# icp.net
KiCad netlist of a schematic drawn in EAGLE
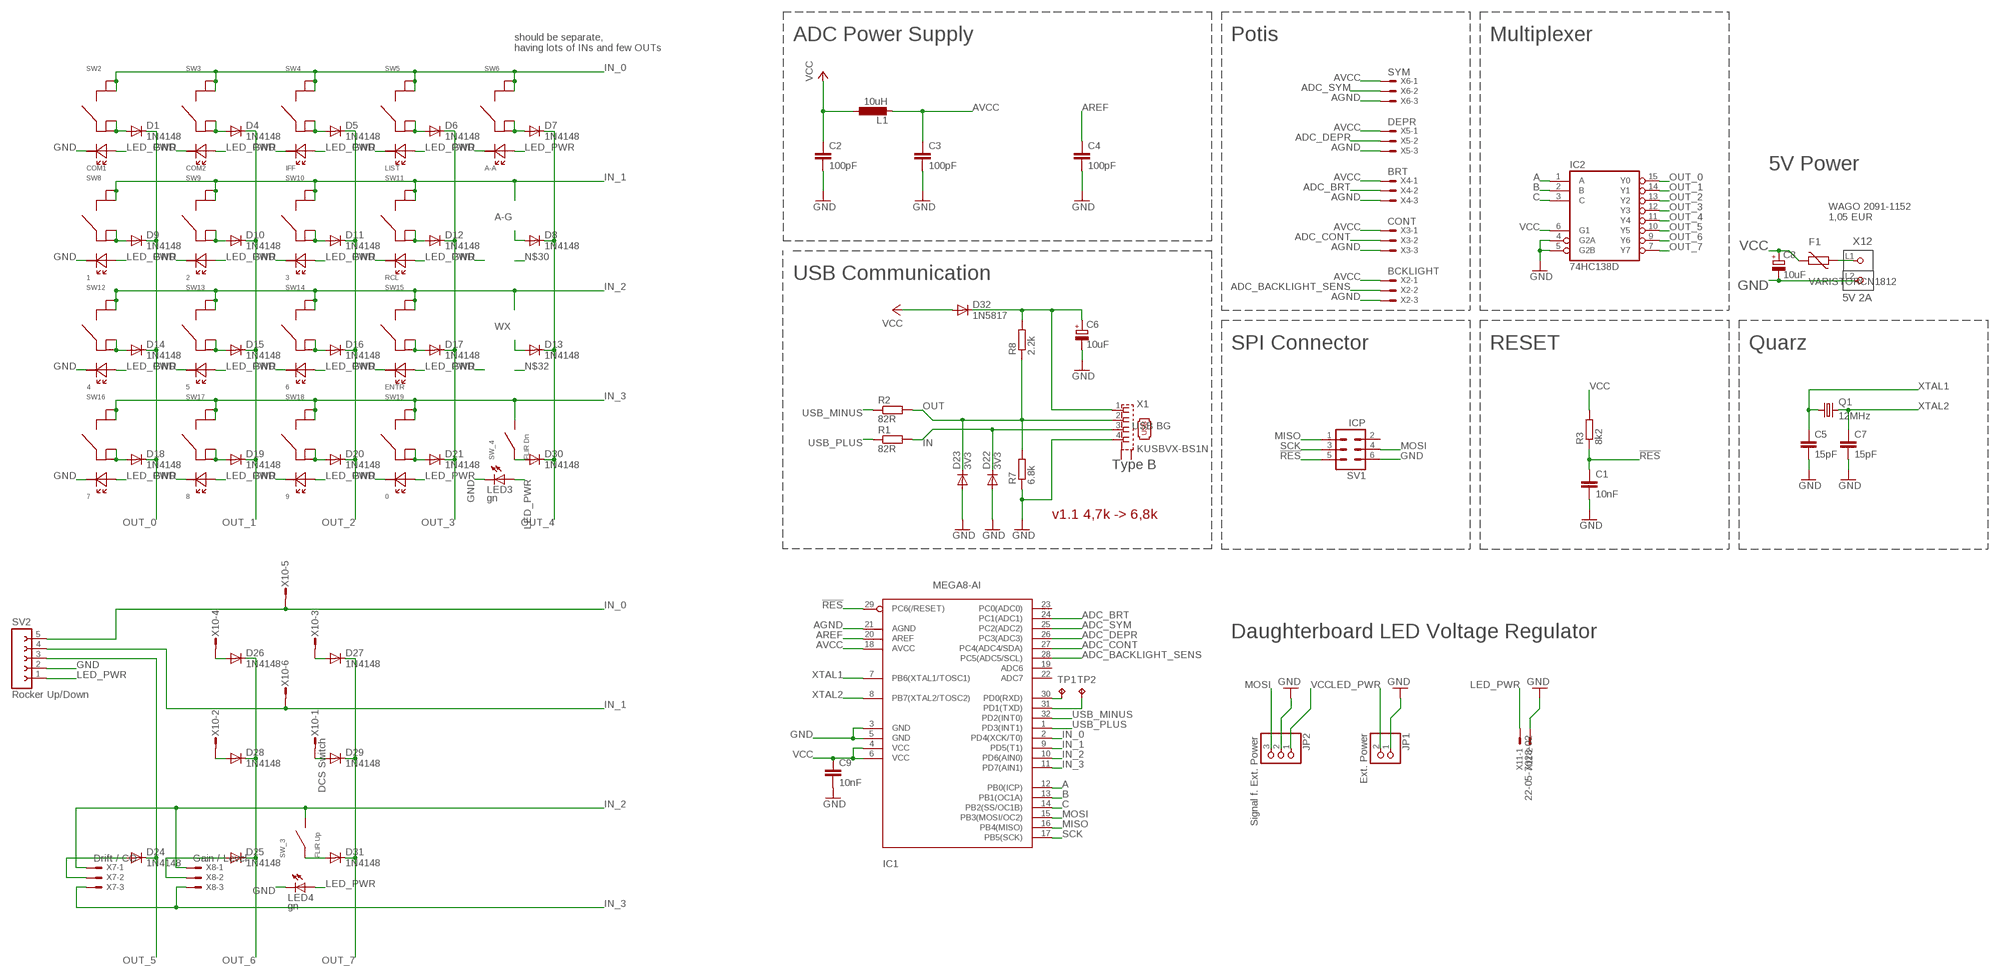
[diagram p0: schematic, sheet 1]

(export (version "E")
  (design (tool "Eeschema 10.0.6"))
  (components
    (comp (ref "C1")
      (value "10nF")
      (footprint "eagle-import:C1206")
      (libsource (lib "eagle-import") (part "C-EUC1206"))
    )
    (comp (ref "C2")
      (value "100pF")
      (footprint "eagle-import:C0805")
      (libsource (lib "eagle-import") (part "C-EUC0805"))
    )
    (comp (ref "C3")
      (value "100pF")
      (footprint "eagle-import:C0805")
      (libsource (lib "eagle-import") (part "C-EUC0805"))
    )
    (comp (ref "C4")
      (value "100pF")
      (footprint "eagle-import:C0805")
      (libsource (lib "eagle-import") (part "C-EUC0805"))
    )
    (comp (ref "C5")
      (value "15pF")
      (footprint "eagle-import:C0805")
      (libsource (lib "eagle-import") (part "C-EUC0805"))
    )
    (comp (ref "C6")
      (value "10uF")
      (footprint "eagle-import:E2-5")
      (libsource (lib "eagle-import") (part "CPOL-EUE2-5"))
    )
    (comp (ref "C7")
      (value "15pF")
      (footprint "eagle-import:C0805")
      (libsource (lib "eagle-import") (part "C-EUC0805"))
    )
    (comp (ref "C8")
      (value "10uF")
      (footprint "eagle-import:E2-5")
      (libsource (lib "eagle-import") (part "CPOL-EUE2-5"))
    )
    (comp (ref "C9")
      (value "10nF")
      (footprint "eagle-import:C1206")
      (libsource (lib "eagle-import") (part "C-EUC1206"))
    )
    (comp (ref "D1")
      (value "1N4148")
      (footprint "eagle-import:DO35-10")
      (libsource (lib "eagle-import") (part "DIODE-DO35-10"))
    )
    (comp (ref "D4")
      (value "1N4148")
      (footprint "eagle-import:DO35-10")
      (libsource (lib "eagle-import") (part "DIODE-DO35-10"))
    )
    (comp (ref "D5")
      (value "1N4148")
      (footprint "eagle-import:DO35-10")
      (libsource (lib "eagle-import") (part "DIODE-DO35-10"))
    )
    (comp (ref "D6")
      (value "1N4148")
      (footprint "eagle-import:DO35-10")
      (libsource (lib "eagle-import") (part "DIODE-DO35-10"))
    )
    (comp (ref "D7")
      (value "1N4148")
      (footprint "eagle-import:DO35-10")
      (libsource (lib "eagle-import") (part "DIODE-DO35-10"))
    )
    (comp (ref "D8")
      (value "1N4148")
      (footprint "eagle-import:DO35-10")
      (libsource (lib "eagle-import") (part "DIODE-DO35-10"))
    )
    (comp (ref "D9")
      (value "1N4148")
      (footprint "eagle-import:DO35-10")
      (libsource (lib "eagle-import") (part "DIODE-DO35-10"))
    )
    (comp (ref "D10")
      (value "1N4148")
      (footprint "eagle-import:DO35-10")
      (libsource (lib "eagle-import") (part "DIODE-DO35-10"))
    )
    (comp (ref "D11")
      (value "1N4148")
      (footprint "eagle-import:DO35-10")
      (libsource (lib "eagle-import") (part "DIODE-DO35-10"))
    )
    (comp (ref "D12")
      (value "1N4148")
      (footprint "eagle-import:DO35-10")
      (libsource (lib "eagle-import") (part "DIODE-DO35-10"))
    )
    (comp (ref "D13")
      (value "1N4148")
      (footprint "eagle-import:DO35-10")
      (libsource (lib "eagle-import") (part "DIODE-DO35-10"))
    )
    (comp (ref "D14")
      (value "1N4148")
      (footprint "eagle-import:DO35-10")
      (libsource (lib "eagle-import") (part "DIODE-DO35-10"))
    )
    (comp (ref "D15")
      (value "1N4148")
      (footprint "eagle-import:DO35-10")
      (libsource (lib "eagle-import") (part "DIODE-DO35-10"))
    )
    (comp (ref "D16")
      (value "1N4148")
      (footprint "eagle-import:DO35-10")
      (libsource (lib "eagle-import") (part "DIODE-DO35-10"))
    )
    (comp (ref "D17")
      (value "1N4148")
      (footprint "eagle-import:DO35-10")
      (libsource (lib "eagle-import") (part "DIODE-DO35-10"))
    )
    (comp (ref "D18")
      (value "1N4148")
      (footprint "eagle-import:DO35-10")
      (libsource (lib "eagle-import") (part "DIODE-DO35-10"))
    )
    (comp (ref "D19")
      (value "1N4148")
      (footprint "eagle-import:DO35-10")
      (libsource (lib "eagle-import") (part "DIODE-DO35-10"))
    )
    (comp (ref "D20")
      (value "1N4148")
      (footprint "eagle-import:DO35-10")
      (libsource (lib "eagle-import") (part "DIODE-DO35-10"))
    )
    (comp (ref "D21")
      (value "1N4148")
      (footprint "eagle-import:DO35-10")
      (libsource (lib "eagle-import") (part "DIODE-DO35-10"))
    )
    (comp (ref "D22")
      (value "3V3")
      (footprint "eagle-import:D-5")
      (libsource (lib "eagle-import") (part "DIODE-D-5"))
    )
    (comp (ref "D23")
      (value "3V3")
      (footprint "eagle-import:D-5")
      (libsource (lib "eagle-import") (part "DIODE-D-5"))
    )
    (comp (ref "D24")
      (value "1N4148")
      (footprint "eagle-import:DO35-10")
      (libsource (lib "eagle-import") (part "DIODE-DO35-10"))
    )
    (comp (ref "D25")
      (value "1N4148")
      (footprint "eagle-import:DO35-10")
      (libsource (lib "eagle-import") (part "DIODE-DO35-10"))
    )
    (comp (ref "D26")
      (value "1N4148")
      (footprint "eagle-import:DO35-10")
      (libsource (lib "eagle-import") (part "DIODE-DO35-10"))
    )
    (comp (ref "D27")
      (value "1N4148")
      (footprint "eagle-import:DO35-10")
      (libsource (lib "eagle-import") (part "DIODE-DO35-10"))
    )
    (comp (ref "D28")
      (value "1N4148")
      (footprint "eagle-import:DO35-10")
      (libsource (lib "eagle-import") (part "DIODE-DO35-10"))
    )
    (comp (ref "D29")
      (value "1N4148")
      (footprint "eagle-import:DO35-10")
      (libsource (lib "eagle-import") (part "DIODE-DO35-10"))
    )
    (comp (ref "D30")
      (value "1N4148")
      (footprint "eagle-import:DO35-10")
      (libsource (lib "eagle-import") (part "DIODE-DO35-10"))
    )
    (comp (ref "D31")
      (value "1N4148")
      (footprint "eagle-import:DO35-10")
      (libsource (lib "eagle-import") (part "DIODE-DO35-10"))
    )
    (comp (ref "D32")
      (value "1N5817")
      (footprint "eagle-import:DO35-10")
      (libsource (lib "eagle-import") (part "DIODE-DO35-10"))
    )
    (comp (ref "F1")
      (value "VARISTORCN1812")
      (footprint "eagle-import:CT_CN1812")
      (libsource (lib "eagle-import") (part "VARISTORCN1812"))
    )
    (comp (ref "IC1")
      (value "MEGA8-AI")
      (footprint "eagle-import:TQFP32-08")
      (libsource (lib "eagle-import") (part "MEGA8-AI"))
    )
    (comp (ref "IC2")
      (value "74HC138D")
      (footprint "eagle-import:SO16")
      (libsource (lib "eagle-import") (part "74138DHC"))
    )
    (comp (ref "JP1")
      (value "Ext. Power")
      (footprint "eagle-import:1X02")
      (libsource (lib "eagle-import") (part "PINHD-1X2"))
    )
    (comp (ref "JP2")
      (value "Signal f. Ext. Power")
      (footprint "eagle-import:1X03")
      (libsource (lib "eagle-import") (part "PINHD-1X3"))
    )
    (comp (ref "L1")
      (value "10uH")
      (footprint "eagle-import:0207_15")
      (libsource (lib "eagle-import") (part "L-EU0207/15"))
    )
    (comp (ref "LED3")
      (value "gn")
      (footprint "eagle-import:CHIPLED_1206")
      (libsource (lib "eagle-import") (part "LEDCHIPLED_1206"))
    )
    (comp (ref "LED4")
      (value "gn")
      (footprint "eagle-import:CHIPLED_1206")
      (libsource (lib "eagle-import") (part "LEDCHIPLED_1206"))
    )
    (comp (ref "Q1")
      (value "12MHz")
      (footprint "eagle-import:HC49U-V")
      (libsource (lib "eagle-import") (part "CRYSTALHC49U-V"))
    )
    (comp (ref "R1")
      (value "82R")
      (footprint "eagle-import:R0805W")
      (libsource (lib "eagle-import") (part "R-EU_R0805W"))
    )
    (comp (ref "R2")
      (value "82R")
      (footprint "eagle-import:R0805W")
      (libsource (lib "eagle-import") (part "R-EU_R0805W"))
    )
    (comp (ref "R3")
      (value "8k2")
      (footprint "eagle-import:R0805")
      (libsource (lib "eagle-import") (part "R-EU_R0805"))
    )
    (comp (ref "R7")
      (value "6.8k")
      (footprint "eagle-import:0207_5V")
      (libsource (lib "eagle-import") (part "R-EU_0207/5V"))
    )
    (comp (ref "R8")
      (value "2.2k")
      (footprint "eagle-import:R0805")
      (libsource (lib "eagle-import") (part "R-EU_R0805"))
    )
    (comp (ref "SV1")
      (value "ICP")
      (footprint "eagle-import:MA03-2")
      (libsource (lib "eagle-import") (part "MA03-2"))
    )
    (comp (ref "SV2")
      (value "Rocker Up/Down")
      (footprint "eagle-import:FE05-1")
      (libsource (lib "eagle-import") (part "FE05-1"))
    )
    (comp (ref "SW2")
      (value "COM1")
      (footprint "eagle-import:3FTL620")
      (libsource (lib "eagle-import") (part "3FTL620"))
    )
    (comp (ref "SW3")
      (value "COM2")
      (footprint "eagle-import:3FTL620")
      (libsource (lib "eagle-import") (part "3FTL620"))
    )
    (comp (ref "SW4")
      (value "IFF")
      (footprint "eagle-import:3FTL620")
      (libsource (lib "eagle-import") (part "3FTL620"))
    )
    (comp (ref "SW5")
      (value "LIST")
      (footprint "eagle-import:3FTL620")
      (libsource (lib "eagle-import") (part "3FTL620"))
    )
    (comp (ref "SW6")
      (value "A-A")
      (footprint "eagle-import:3FTL620")
      (libsource (lib "eagle-import") (part "3FTL620"))
    )
    (comp (ref "SW8")
      (value "1")
      (footprint "eagle-import:3FTL620")
      (libsource (lib "eagle-import") (part "3FTL620"))
    )
    (comp (ref "SW9")
      (value "2")
      (footprint "eagle-import:3FTL620")
      (libsource (lib "eagle-import") (part "3FTL620"))
    )
    (comp (ref "SW10")
      (value "3")
      (footprint "eagle-import:3FTL620")
      (libsource (lib "eagle-import") (part "3FTL620"))
    )
    (comp (ref "SW11")
      (value "RCL")
      (footprint "eagle-import:3FTL620")
      (libsource (lib "eagle-import") (part "3FTL620"))
    )
    (comp (ref "SW12")
      (value "4")
      (footprint "eagle-import:3FTL620")
      (libsource (lib "eagle-import") (part "3FTL620"))
    )
    (comp (ref "SW13")
      (value "5")
      (footprint "eagle-import:3FTL620")
      (libsource (lib "eagle-import") (part "3FTL620"))
    )
    (comp (ref "SW14")
      (value "6")
      (footprint "eagle-import:3FTL620")
      (libsource (lib "eagle-import") (part "3FTL620"))
    )
    (comp (ref "SW15")
      (value "ENTR")
      (footprint "eagle-import:3FTL620")
      (libsource (lib "eagle-import") (part "3FTL620"))
    )
    (comp (ref "SW16")
      (value "7")
      (footprint "eagle-import:3FTL620")
      (libsource (lib "eagle-import") (part "3FTL620"))
    )
    (comp (ref "SW17")
      (value "8")
      (footprint "eagle-import:3FTL620")
      (libsource (lib "eagle-import") (part "3FTL620"))
    )
    (comp (ref "SW18")
      (value "9")
      (footprint "eagle-import:3FTL620")
      (libsource (lib "eagle-import") (part "3FTL620"))
    )
    (comp (ref "SW19")
      (value "0")
      (footprint "eagle-import:3FTL620")
      (libsource (lib "eagle-import") (part "3FTL620"))
    )
    (comp (ref "SW_3")
      (value "FLIR Up")
      (footprint "eagle-import:TYPE_A")
      (libsource (lib "eagle-import") (part "APEM_SWITCH"))
    )
    (comp (ref "SW_4")
      (value "FLIR Dn")
      (footprint "eagle-import:TYPE_A")
      (libsource (lib "eagle-import") (part "APEM_SWITCH"))
    )
    (comp (ref "TP1")
      (value "TPTP06SQ")
      (footprint "eagle-import:TP06SQ")
      (libsource (lib "eagle-import") (part "TPTP06SQ"))
    )
    (comp (ref "TP2")
      (value "TPTP06SQ")
      (footprint "eagle-import:TP06SQ")
      (libsource (lib "eagle-import") (part "TPTP06SQ"))
    )
    (comp (ref "X1")
      (value "KUSBVX-BS1N")
      (footprint "eagle-import:KUSBVX-BS1N")
      (fields (field (name "REICHELT") "USB BG"))
      (libsource (lib "eagle-import") (part "KUSBVX-BS1N"))
    )
    (comp (ref "X2")
      (value "BCKLIGHT")
      (footprint "eagle-import:22-23-2031")
      (fields (field (name "MF") "MOLEX") (field (name "MPN") "22-23-2031"))
      (libsource (lib "eagle-import") (part "22-23-2031"))
    )
    (comp (ref "X3")
      (value "CONT")
      (footprint "eagle-import:22-23-2031")
      (fields (field (name "MF") "MOLEX") (field (name "MPN") "22-23-2031"))
      (libsource (lib "eagle-import") (part "22-23-2031"))
    )
    (comp (ref "X4")
      (value "BRT")
      (footprint "eagle-import:22-23-2031")
      (fields (field (name "MF") "MOLEX") (field (name "MPN") "22-23-2031"))
      (libsource (lib "eagle-import") (part "22-23-2031"))
    )
    (comp (ref "X5")
      (value "DEPR")
      (footprint "eagle-import:22-23-2031")
      (fields (field (name "MF") "MOLEX") (field (name "MPN") "22-23-2031"))
      (libsource (lib "eagle-import") (part "22-23-2031"))
    )
    (comp (ref "X6")
      (value "SYM")
      (footprint "eagle-import:22-23-2031")
      (fields (field (name "MF") "MOLEX") (field (name "MPN") "22-23-2031"))
      (libsource (lib "eagle-import") (part "22-23-2031"))
    )
    (comp (ref "X7")
      (value "Drift / CO")
      (footprint "eagle-import:22-23-2031")
      (fields
        (field (name "MF") "MOLEX")
        (field (name "MPN") "22-23-2031")
        (field (name "MF_1") "MOLEX")
        (field (name "MPN_1") "22-23-2031")
        (field (name "OC_FARNELL") "1462950")
        (field (name "OC_NEWARK") "30C0862")
      )
      (libsource (lib "eagle-import") (part "22-23-2031"))
    )
    (comp (ref "X8")
      (value "Gain / Level")
      (footprint "eagle-import:22-23-2031")
      (fields
        (field (name "MF") "MOLEX")
        (field (name "MPN") "22-23-2031")
        (field (name "MF_1") "MOLEX")
        (field (name "MPN_1") "22-23-2031")
        (field (name "OC_FARNELL") "1462950")
        (field (name "OC_NEWARK") "30C0862")
      )
      (libsource (lib "eagle-import") (part "22-23-2031"))
    )
    (comp (ref "X10")
      (value "DCS Switch")
      (footprint "eagle-import:MICROMATCH-6")
      (fields (field (name "MPN") "7-215464-6"))
      (libsource (lib "eagle-import") (part "MICROMATCH-6"))
    )
    (comp (ref "X11")
      (value "22-05-7028-02")
      (footprint "eagle-import:7395-02")
      (fields (field (name "OC_FARNELL") "9731601") (field (name "OC_NEWARK") "unknown"))
      (libsource (lib "eagle-import") (part "22-?-0205-7028"))
    )
    (comp (ref "X12")
      (value "5V 2A")
      (footprint "eagle-import:P-2091-1152")
      (libsource (lib "eagle-import") (part "2091-1152"))
    )
  )
  (nets
    (net (code "1") (name "/A") (class "Default")
      (node (ref "IC1") (pin "12") (pinfunction "PB0(ICP)_12") (pintype "bidirectional"))
      (node (ref "IC2") (pin "1") (pinfunction "A_1") (pintype "input"))
    )
    (net (code "2") (name "/ADC_BACKLIGHT_SENS") (class "Default")
      (node (ref "IC1") (pin "28") (pinfunction "PC5(ADC5/SCL)_28") (pintype "bidirectional"))
      (node (ref "X2") (pin "2") (pinfunction "S_2") (pintype "passive"))
    )
    (net (code "3") (name "/ADC_BRT") (class "Default")
      (node (ref "IC1") (pin "24") (pinfunction "PC1(ADC1)_24") (pintype "bidirectional"))
      (node (ref "X4") (pin "2") (pinfunction "S_2") (pintype "passive"))
    )
    (net (code "4") (name "/ADC_CONT") (class "Default")
      (node (ref "IC1") (pin "27") (pinfunction "PC4(ADC4/SDA)_27") (pintype "bidirectional"))
      (node (ref "X3") (pin "2") (pinfunction "S_2") (pintype "passive"))
    )
    (net (code "5") (name "/ADC_DEPR") (class "Default")
      (node (ref "IC1") (pin "26") (pinfunction "PC3(ADC3)_26") (pintype "bidirectional"))
      (node (ref "X5") (pin "2") (pinfunction "S_2") (pintype "passive"))
    )
    (net (code "6") (name "/ADC_SYM") (class "Default")
      (node (ref "IC1") (pin "25") (pinfunction "PC2(ADC2)_25") (pintype "bidirectional"))
      (node (ref "X6") (pin "2") (pinfunction "S_2") (pintype "passive"))
    )
    (net (code "7") (name "/AGND") (class "Default")
      (node (ref "IC1") (pin "21") (pinfunction "AGND_21") (pintype "bidirectional"))
      (node (ref "X2") (pin "3") (pinfunction "S_3") (pintype "passive"))
      (node (ref "X3") (pin "3") (pinfunction "S_3") (pintype "passive"))
      (node (ref "X4") (pin "3") (pinfunction "S_3") (pintype "passive"))
      (node (ref "X5") (pin "3") (pinfunction "S_3") (pintype "passive"))
      (node (ref "X6") (pin "3") (pinfunction "S_3") (pintype "passive"))
    )
    (net (code "8") (name "/AREF") (class "Default")
      (node (ref "C4") (pin "1") (pinfunction "1_1") (pintype "passive"))
      (node (ref "IC1") (pin "20") (pinfunction "AREF_20") (pintype "bidirectional"))
    )
    (net (code "9") (name "/AVCC") (class "Default")
      (node (ref "C3") (pin "1") (pinfunction "1_1") (pintype "passive"))
      (node (ref "IC1") (pin "18") (pinfunction "AVCC_18") (pintype "bidirectional"))
      (node (ref "L1") (pin "2") (pinfunction "2_2") (pintype "passive"))
      (node (ref "X2") (pin "1") (pinfunction "S_1") (pintype "passive"))
      (node (ref "X3") (pin "1") (pinfunction "S_1") (pintype "passive"))
      (node (ref "X4") (pin "1") (pinfunction "S_1") (pintype "passive"))
      (node (ref "X5") (pin "1") (pinfunction "S_1") (pintype "passive"))
      (node (ref "X6") (pin "1") (pinfunction "S_1") (pintype "passive"))
    )
    (net (code "10") (name "/B") (class "Default")
      (node (ref "IC1") (pin "13") (pinfunction "PB1(OC1A)_13") (pintype "bidirectional"))
      (node (ref "IC2") (pin "2") (pinfunction "B_2") (pintype "input"))
    )
    (net (code "11") (name "/C") (class "Default")
      (node (ref "IC1") (pin "14") (pinfunction "PB2(SS/OC1B)_14") (pintype "bidirectional"))
      (node (ref "IC2") (pin "3") (pinfunction "C_3") (pintype "input"))
    )
    (net (code "12") (name "/IN") (class "Default")
      (node (ref "D22") (pin "C") (pinfunction "C_C") (pintype "passive"))
      (node (ref "R1") (pin "2") (pinfunction "2_2") (pintype "passive"))
      (node (ref "X1") (pin "3") (pinfunction "3_3") (pintype "passive"))
    )
    (net (code "13") (name "/IN_0") (class "Default")
      (node (ref "IC1") (pin "2") (pinfunction "PD4(XCK/T0)_2") (pintype "bidirectional"))
      (node (ref "SV2") (pin "5") (pinfunction "5_5") (pintype "passive"))
      (node (ref "SW2") (pin "P$1") (pinfunction "P$1_P$1") (pintype "passive"))
      (node (ref "SW2") (pin "P$3") (pinfunction "P$3_P$3") (pintype "passive"))
      (node (ref "SW3") (pin "P$1") (pinfunction "P$1_P$1") (pintype "passive"))
      (node (ref "SW3") (pin "P$3") (pinfunction "P$3_P$3") (pintype "passive"))
      (node (ref "SW4") (pin "P$1") (pinfunction "P$1_P$1") (pintype "passive"))
      (node (ref "SW4") (pin "P$3") (pinfunction "P$3_P$3") (pintype "passive"))
      (node (ref "SW5") (pin "P$1") (pinfunction "P$1_P$1") (pintype "passive"))
      (node (ref "SW5") (pin "P$3") (pinfunction "P$3_P$3") (pintype "passive"))
      (node (ref "SW6") (pin "P$1") (pinfunction "P$1_P$1") (pintype "passive"))
      (node (ref "SW6") (pin "P$3") (pinfunction "P$3_P$3") (pintype "passive"))
      (node (ref "X10") (pin "5") (pinfunction "S_5") (pintype "passive"))
    )
    (net (code "14") (name "/IN_1") (class "Default")
      (node (ref "IC1") (pin "9") (pinfunction "PD5(T1)_9") (pintype "bidirectional"))
      (node (ref "SV2") (pin "4") (pinfunction "4_4") (pintype "passive"))
      (node (ref "SW10") (pin "P$1") (pinfunction "P$1_P$1") (pintype "passive"))
      (node (ref "SW10") (pin "P$3") (pinfunction "P$3_P$3") (pintype "passive"))
      (node (ref "SW11") (pin "P$1") (pinfunction "P$1_P$1") (pintype "passive"))
      (node (ref "SW11") (pin "P$3") (pinfunction "P$3_P$3") (pintype "passive"))
      (node (ref "SW8") (pin "P$1") (pinfunction "P$1_P$1") (pintype "passive"))
      (node (ref "SW8") (pin "P$3") (pinfunction "P$3_P$3") (pintype "passive"))
      (node (ref "SW9") (pin "P$1") (pinfunction "P$1_P$1") (pintype "passive"))
      (node (ref "SW9") (pin "P$3") (pinfunction "P$3_P$3") (pintype "passive"))
      (node (ref "X10") (pin "6") (pinfunction "S_6") (pintype "passive"))
    )
    (net (code "15") (name "/IN_2") (class "Default")
      (node (ref "IC1") (pin "10") (pinfunction "PD6(AIN0)_10") (pintype "bidirectional"))
      (node (ref "SW12") (pin "P$1") (pinfunction "P$1_P$1") (pintype "passive"))
      (node (ref "SW12") (pin "P$3") (pinfunction "P$3_P$3") (pintype "passive"))
      (node (ref "SW13") (pin "P$1") (pinfunction "P$1_P$1") (pintype "passive"))
      (node (ref "SW13") (pin "P$3") (pinfunction "P$3_P$3") (pintype "passive"))
      (node (ref "SW14") (pin "P$1") (pinfunction "P$1_P$1") (pintype "passive"))
      (node (ref "SW14") (pin "P$3") (pinfunction "P$3_P$3") (pintype "passive"))
      (node (ref "SW15") (pin "P$1") (pinfunction "P$1_P$1") (pintype "passive"))
      (node (ref "SW15") (pin "P$3") (pinfunction "P$3_P$3") (pintype "passive"))
      (node (ref "SW_3") (pin "P$1") (pinfunction "P$1_P$1") (pintype "passive"))
      (node (ref "X7") (pin "1") (pinfunction "S_1") (pintype "passive"))
      (node (ref "X8") (pin "1") (pinfunction "S_1") (pintype "passive"))
    )
    (net (code "16") (name "/IN_3") (class "Default")
      (node (ref "IC1") (pin "11") (pinfunction "PD7(AIN1)_11") (pintype "bidirectional"))
      (node (ref "SW16") (pin "P$1") (pinfunction "P$1_P$1") (pintype "passive"))
      (node (ref "SW16") (pin "P$3") (pinfunction "P$3_P$3") (pintype "passive"))
      (node (ref "SW17") (pin "P$1") (pinfunction "P$1_P$1") (pintype "passive"))
      (node (ref "SW17") (pin "P$3") (pinfunction "P$3_P$3") (pintype "passive"))
      (node (ref "SW18") (pin "P$1") (pinfunction "P$1_P$1") (pintype "passive"))
      (node (ref "SW18") (pin "P$3") (pinfunction "P$3_P$3") (pintype "passive"))
      (node (ref "SW19") (pin "P$1") (pinfunction "P$1_P$1") (pintype "passive"))
      (node (ref "SW19") (pin "P$3") (pinfunction "P$3_P$3") (pintype "passive"))
      (node (ref "SW_4") (pin "P$1") (pinfunction "P$1_P$1") (pintype "passive"))
      (node (ref "X7") (pin "3") (pinfunction "S_3") (pintype "passive"))
      (node (ref "X8") (pin "3") (pinfunction "S_3") (pintype "passive"))
    )
    (net (code "17") (name "/LED_PWR") (class "Default")
      (node (ref "JP1") (pin "2") (pinfunction "2_2") (pintype "passive"))
      (node (ref "LED3") (pin "A") (pinfunction "A_A") (pintype "passive"))
      (node (ref "LED4") (pin "A") (pinfunction "A_A") (pintype "passive"))
      (node (ref "SV2") (pin "1") (pinfunction "1_1") (pintype "passive"))
      (node (ref "SW10") (pin "P$5") (pinfunction "LED$3_P$5") (pintype "passive"))
      (node (ref "SW11") (pin "P$5") (pinfunction "LED$3_P$5") (pintype "passive"))
      (node (ref "SW12") (pin "P$5") (pinfunction "LED$3_P$5") (pintype "passive"))
      (node (ref "SW13") (pin "P$5") (pinfunction "LED$3_P$5") (pintype "passive"))
      (node (ref "SW14") (pin "P$5") (pinfunction "LED$3_P$5") (pintype "passive"))
      (node (ref "SW15") (pin "P$5") (pinfunction "LED$3_P$5") (pintype "passive"))
      (node (ref "SW16") (pin "P$5") (pinfunction "LED$3_P$5") (pintype "passive"))
      (node (ref "SW17") (pin "P$5") (pinfunction "LED$3_P$5") (pintype "passive"))
      (node (ref "SW18") (pin "P$5") (pinfunction "LED$3_P$5") (pintype "passive"))
      (node (ref "SW19") (pin "P$5") (pinfunction "LED$3_P$5") (pintype "passive"))
      (node (ref "SW2") (pin "P$5") (pinfunction "LED$3_P$5") (pintype "passive"))
      (node (ref "SW3") (pin "P$5") (pinfunction "LED$3_P$5") (pintype "passive"))
      (node (ref "SW4") (pin "P$5") (pinfunction "LED$3_P$5") (pintype "passive"))
      (node (ref "SW5") (pin "P$5") (pinfunction "LED$3_P$5") (pintype "passive"))
      (node (ref "SW6") (pin "P$5") (pinfunction "LED$3_P$5") (pintype "passive"))
      (node (ref "SW8") (pin "P$5") (pinfunction "LED$3_P$5") (pintype "passive"))
      (node (ref "SW9") (pin "P$5") (pinfunction "LED$3_P$5") (pintype "passive"))
      (node (ref "X11") (pin "1") (pinfunction "S_1") (pintype "passive"))
    )
    (net (code "18") (name "/MISO") (class "Default")
      (node (ref "IC1") (pin "16") (pinfunction "PB4(MISO)_16") (pintype "bidirectional"))
      (node (ref "SV1") (pin "1") (pinfunction "1_1") (pintype "passive"))
    )
    (net (code "19") (name "/MOSI") (class "Default")
      (node (ref "IC1") (pin "15") (pinfunction "PB3(MOSI/OC2)_15") (pintype "bidirectional"))
      (node (ref "JP2") (pin "3") (pinfunction "3_3") (pintype "passive"))
      (node (ref "SV1") (pin "4") (pinfunction "4_4") (pintype "passive"))
    )
    (net (code "22") (name "/OUT") (class "Default")
      (node (ref "D23") (pin "C") (pinfunction "C_C") (pintype "passive"))
      (node (ref "R2") (pin "2") (pinfunction "2_2") (pintype "passive"))
      (node (ref "R7") (pin "2") (pinfunction "2_2") (pintype "passive"))
      (node (ref "R8") (pin "1") (pinfunction "1_1") (pintype "passive"))
      (node (ref "X1") (pin "2") (pinfunction "2_2") (pintype "passive"))
    )
    (net (code "23") (name "/OUT_0") (class "Default")
      (node (ref "D1") (pin "C") (pinfunction "C_C") (pintype "passive"))
      (node (ref "D14") (pin "C") (pinfunction "C_C") (pintype "passive"))
      (node (ref "D18") (pin "C") (pinfunction "C_C") (pintype "passive"))
      (node (ref "D9") (pin "C") (pinfunction "C_C") (pintype "passive"))
      (node (ref "IC2") (pin "15") (pinfunction "Y0_15") (pintype "output"))
    )
    (net (code "24") (name "/OUT_1") (class "Default")
      (node (ref "D10") (pin "C") (pinfunction "C_C") (pintype "passive"))
      (node (ref "D15") (pin "C") (pinfunction "C_C") (pintype "passive"))
      (node (ref "D19") (pin "C") (pinfunction "C_C") (pintype "passive"))
      (node (ref "D4") (pin "C") (pinfunction "C_C") (pintype "passive"))
      (node (ref "IC2") (pin "14") (pinfunction "Y1_14") (pintype "output"))
    )
    (net (code "25") (name "/OUT_2") (class "Default")
      (node (ref "D11") (pin "C") (pinfunction "C_C") (pintype "passive"))
      (node (ref "D16") (pin "C") (pinfunction "C_C") (pintype "passive"))
      (node (ref "D20") (pin "C") (pinfunction "C_C") (pintype "passive"))
      (node (ref "D5") (pin "C") (pinfunction "C_C") (pintype "passive"))
      (node (ref "IC2") (pin "13") (pinfunction "Y2_13") (pintype "output"))
    )
    (net (code "26") (name "/OUT_3") (class "Default")
      (node (ref "D12") (pin "C") (pinfunction "C_C") (pintype "passive"))
      (node (ref "D17") (pin "C") (pinfunction "C_C") (pintype "passive"))
      (node (ref "D21") (pin "C") (pinfunction "C_C") (pintype "passive"))
      (node (ref "D6") (pin "C") (pinfunction "C_C") (pintype "passive"))
      (node (ref "IC2") (pin "12") (pinfunction "Y3_12") (pintype "output"))
    )
    (net (code "27") (name "/OUT_4") (class "Default")
      (node (ref "D13") (pin "C") (pinfunction "C_C") (pintype "passive"))
      (node (ref "D30") (pin "C") (pinfunction "C_C") (pintype "passive"))
      (node (ref "D7") (pin "C") (pinfunction "C_C") (pintype "passive"))
      (node (ref "D8") (pin "C") (pinfunction "C_C") (pintype "passive"))
      (node (ref "IC2") (pin "11") (pinfunction "Y4_11") (pintype "output"))
    )
    (net (code "28") (name "/OUT_5") (class "Default")
      (node (ref "D24") (pin "C") (pinfunction "C_C") (pintype "passive"))
      (node (ref "IC2") (pin "10") (pinfunction "Y5_10") (pintype "output"))
      (node (ref "SV2") (pin "3") (pinfunction "3_3") (pintype "passive"))
    )
    (net (code "29") (name "/OUT_6") (class "Default")
      (node (ref "D25") (pin "C") (pinfunction "C_C") (pintype "passive"))
      (node (ref "D26") (pin "C") (pinfunction "C_C") (pintype "passive"))
      (node (ref "D28") (pin "C") (pinfunction "C_C") (pintype "passive"))
      (node (ref "IC2") (pin "9") (pinfunction "Y6_9") (pintype "output"))
    )
    (net (code "30") (name "/OUT_7") (class "Default")
      (node (ref "D27") (pin "C") (pinfunction "C_C") (pintype "passive"))
      (node (ref "D29") (pin "C") (pinfunction "C_C") (pintype "passive"))
      (node (ref "D31") (pin "C") (pinfunction "C_C") (pintype "passive"))
      (node (ref "IC2") (pin "7") (pinfunction "Y7_7") (pintype "output"))
    )
    (net (code "31") (name "/SCK") (class "Default")
      (node (ref "IC1") (pin "17") (pinfunction "PB5(SCK)_17") (pintype "bidirectional"))
      (node (ref "SV1") (pin "3") (pinfunction "3_3") (pintype "passive"))
    )
    (net (code "32") (name "/USB_MINUS") (class "Default")
      (node (ref "IC1") (pin "32") (pinfunction "PD2(INT0)_32") (pintype "bidirectional"))
      (node (ref "R2") (pin "1") (pinfunction "1_1") (pintype "passive"))
    )
    (net (code "33") (name "/USB_PLUS") (class "Default")
      (node (ref "IC1") (pin "1") (pinfunction "PD3(INT1)_1") (pintype "bidirectional"))
      (node (ref "R1") (pin "1") (pinfunction "1_1") (pintype "passive"))
    )
    (net (code "34") (name "/XTAL1") (class "Default")
      (node (ref "C5") (pin "1") (pinfunction "1_1") (pintype "passive"))
      (node (ref "IC1") (pin "7") (pinfunction "PB6(XTAL1/TOSC1)_7") (pintype "bidirectional"))
      (node (ref "Q1") (pin "1") (pinfunction "1_1") (pintype "passive"))
    )
    (net (code "35") (name "/XTAL2") (class "Default")
      (node (ref "C7") (pin "1") (pinfunction "1_1") (pintype "passive"))
      (node (ref "IC1") (pin "8") (pinfunction "PB7(XTAL2/TOSC2)_8") (pintype "bidirectional"))
      (node (ref "Q1") (pin "2") (pinfunction "2_2") (pintype "passive"))
    )
    (net (code "36") (name "/~{RES}") (class "Default")
      (node (ref "C1") (pin "1") (pinfunction "1_1") (pintype "passive"))
      (node (ref "IC1") (pin "29") (pinfunction "PC6(/RESET)_29") (pintype "bidirectional"))
      (node (ref "R3") (pin "1") (pinfunction "1_1") (pintype "passive"))
      (node (ref "SV1") (pin "5") (pinfunction "5_5") (pintype "passive"))
    )
    (net (code "37") (name "GND") (class "Default")
      (node (ref "C1") (pin "2") (pinfunction "2_2") (pintype "passive"))
      (node (ref "C2") (pin "2") (pinfunction "2_2") (pintype "passive"))
      (node (ref "C3") (pin "2") (pinfunction "2_2") (pintype "passive"))
      (node (ref "C4") (pin "2") (pinfunction "2_2") (pintype "passive"))
      (node (ref "C5") (pin "2") (pinfunction "2_2") (pintype "passive"))
      (node (ref "C6") (pin "-") (pinfunction "-_-") (pintype "passive"))
      (node (ref "C7") (pin "2") (pinfunction "2_2") (pintype "passive"))
      (node (ref "C8") (pin "-") (pinfunction "-_-") (pintype "passive"))
      (node (ref "C9") (pin "2") (pinfunction "2_2") (pintype "passive"))
      (node (ref "D22") (pin "A") (pinfunction "A_A") (pintype "passive"))
      (node (ref "D23") (pin "A") (pinfunction "A_A") (pintype "passive"))
      (node (ref "IC1") (pin "3") (pinfunction "GND_3") (pintype "bidirectional"))
      (node (ref "IC1") (pin "5") (pinfunction "GND_5") (pintype "bidirectional"))
      (node (ref "IC2") (pin "4") (pinfunction "G2A_4") (pintype "input"))
      (node (ref "IC2") (pin "5") (pinfunction "G2B_5") (pintype "input"))
      (node (ref "JP1") (pin "1") (pinfunction "1_1") (pintype "passive"))
      (node (ref "JP2") (pin "2") (pinfunction "2_2") (pintype "passive"))
      (node (ref "LED3") (pin "C") (pinfunction "C_C") (pintype "passive"))
      (node (ref "LED4") (pin "C") (pinfunction "C_C") (pintype "passive"))
      (node (ref "R7") (pin "1") (pinfunction "1_1") (pintype "passive"))
      (node (ref "SV1") (pin "6") (pinfunction "6_6") (pintype "passive"))
      (node (ref "SV2") (pin "2") (pinfunction "2_2") (pintype "passive"))
      (node (ref "SW10") (pin "P$6") (pinfunction "LED$4_P$6") (pintype "passive"))
      (node (ref "SW11") (pin "P$6") (pinfunction "LED$4_P$6") (pintype "passive"))
      (node (ref "SW12") (pin "P$6") (pinfunction "LED$4_P$6") (pintype "passive"))
      (node (ref "SW13") (pin "P$6") (pinfunction "LED$4_P$6") (pintype "passive"))
      (node (ref "SW14") (pin "P$6") (pinfunction "LED$4_P$6") (pintype "passive"))
      (node (ref "SW15") (pin "P$6") (pinfunction "LED$4_P$6") (pintype "passive"))
      (node (ref "SW16") (pin "P$6") (pinfunction "LED$4_P$6") (pintype "passive"))
      (node (ref "SW17") (pin "P$6") (pinfunction "LED$4_P$6") (pintype "passive"))
      (node (ref "SW18") (pin "P$6") (pinfunction "LED$4_P$6") (pintype "passive"))
      (node (ref "SW19") (pin "P$6") (pinfunction "LED$4_P$6") (pintype "passive"))
      (node (ref "SW2") (pin "P$6") (pinfunction "LED$4_P$6") (pintype "passive"))
      (node (ref "SW3") (pin "P$6") (pinfunction "LED$4_P$6") (pintype "passive"))
      (node (ref "SW4") (pin "P$6") (pinfunction "LED$4_P$6") (pintype "passive"))
      (node (ref "SW5") (pin "P$6") (pinfunction "LED$4_P$6") (pintype "passive"))
      (node (ref "SW6") (pin "P$6") (pinfunction "LED$4_P$6") (pintype "passive"))
      (node (ref "SW8") (pin "P$6") (pinfunction "LED$4_P$6") (pintype "passive"))
      (node (ref "SW9") (pin "P$6") (pinfunction "LED$4_P$6") (pintype "passive"))
      (node (ref "X1") (pin "4") (pinfunction "4_4") (pintype "passive"))
      (node (ref "X11") (pin "2") (pinfunction "S_2") (pintype "passive"))
      (node (ref "X12") (pin "L2") (pinfunction "P2_L2") (pintype "bidirectional"))
    )
    (net (code "38") (name "Net-(C6-Pad+)") (class "Default")
      (node (ref "C6") (pin "+") (pinfunction "+_+") (pintype "passive"))
      (node (ref "D32") (pin "C") (pinfunction "C_C") (pintype "passive"))
      (node (ref "R8") (pin "2") (pinfunction "2_2") (pintype "passive"))
      (node (ref "X1") (pin "1") (pinfunction "1_1") (pintype "passive"))
    )
    (net (code "39") (name "Net-(D1-PadA)") (class "Default")
      (node (ref "D1") (pin "A") (pinfunction "A_A") (pintype "passive"))
      (node (ref "SW2") (pin "P$2") (pinfunction "P$2_P$2") (pintype "passive"))
      (node (ref "SW2") (pin "P$4") (pinfunction "P$4_P$4") (pintype "passive"))
    )
    (net (code "40") (name "Net-(D4-PadA)") (class "Default")
      (node (ref "D4") (pin "A") (pinfunction "A_A") (pintype "passive"))
      (node (ref "SW3") (pin "P$2") (pinfunction "P$2_P$2") (pintype "passive"))
      (node (ref "SW3") (pin "P$4") (pinfunction "P$4_P$4") (pintype "passive"))
    )
    (net (code "41") (name "Net-(D5-PadA)") (class "Default")
      (node (ref "D5") (pin "A") (pinfunction "A_A") (pintype "passive"))
      (node (ref "SW4") (pin "P$2") (pinfunction "P$2_P$2") (pintype "passive"))
      (node (ref "SW4") (pin "P$4") (pinfunction "P$4_P$4") (pintype "passive"))
    )
    (net (code "42") (name "Net-(D6-PadA)") (class "Default")
      (node (ref "D6") (pin "A") (pinfunction "A_A") (pintype "passive"))
      (node (ref "SW5") (pin "P$2") (pinfunction "P$2_P$2") (pintype "passive"))
      (node (ref "SW5") (pin "P$4") (pinfunction "P$4_P$4") (pintype "passive"))
    )
    (net (code "43") (name "Net-(D7-PadA)") (class "Default")
      (node (ref "D7") (pin "A") (pinfunction "A_A") (pintype "passive"))
      (node (ref "SW6") (pin "P$2") (pinfunction "P$2_P$2") (pintype "passive"))
      (node (ref "SW6") (pin "P$4") (pinfunction "P$4_P$4") (pintype "passive"))
    )
    (net (code "44") (name "Net-(D9-PadA)") (class "Default")
      (node (ref "D9") (pin "A") (pinfunction "A_A") (pintype "passive"))
      (node (ref "SW8") (pin "P$2") (pinfunction "P$2_P$2") (pintype "passive"))
      (node (ref "SW8") (pin "P$4") (pinfunction "P$4_P$4") (pintype "passive"))
    )
    (net (code "45") (name "Net-(D10-PadA)") (class "Default")
      (node (ref "D10") (pin "A") (pinfunction "A_A") (pintype "passive"))
      (node (ref "SW9") (pin "P$2") (pinfunction "P$2_P$2") (pintype "passive"))
      (node (ref "SW9") (pin "P$4") (pinfunction "P$4_P$4") (pintype "passive"))
    )
    (net (code "46") (name "Net-(D11-PadA)") (class "Default")
      (node (ref "D11") (pin "A") (pinfunction "A_A") (pintype "passive"))
      (node (ref "SW10") (pin "P$2") (pinfunction "P$2_P$2") (pintype "passive"))
      (node (ref "SW10") (pin "P$4") (pinfunction "P$4_P$4") (pintype "passive"))
    )
    (net (code "47") (name "Net-(D12-PadA)") (class "Default")
      (node (ref "D12") (pin "A") (pinfunction "A_A") (pintype "passive"))
      (node (ref "SW11") (pin "P$2") (pinfunction "P$2_P$2") (pintype "passive"))
      (node (ref "SW11") (pin "P$4") (pinfunction "P$4_P$4") (pintype "passive"))
    )
    (net (code "48") (name "Net-(D14-PadA)") (class "Default")
      (node (ref "D14") (pin "A") (pinfunction "A_A") (pintype "passive"))
      (node (ref "SW12") (pin "P$2") (pinfunction "P$2_P$2") (pintype "passive"))
      (node (ref "SW12") (pin "P$4") (pinfunction "P$4_P$4") (pintype "passive"))
    )
    (net (code "49") (name "Net-(D15-PadA)") (class "Default")
      (node (ref "D15") (pin "A") (pinfunction "A_A") (pintype "passive"))
      (node (ref "SW13") (pin "P$2") (pinfunction "P$2_P$2") (pintype "passive"))
      (node (ref "SW13") (pin "P$4") (pinfunction "P$4_P$4") (pintype "passive"))
    )
    (net (code "50") (name "Net-(D16-PadA)") (class "Default")
      (node (ref "D16") (pin "A") (pinfunction "A_A") (pintype "passive"))
      (node (ref "SW14") (pin "P$2") (pinfunction "P$2_P$2") (pintype "passive"))
      (node (ref "SW14") (pin "P$4") (pinfunction "P$4_P$4") (pintype "passive"))
    )
    (net (code "51") (name "Net-(D17-PadA)") (class "Default")
      (node (ref "D17") (pin "A") (pinfunction "A_A") (pintype "passive"))
      (node (ref "SW15") (pin "P$2") (pinfunction "P$2_P$2") (pintype "passive"))
      (node (ref "SW15") (pin "P$4") (pinfunction "P$4_P$4") (pintype "passive"))
    )
    (net (code "52") (name "Net-(D18-PadA)") (class "Default")
      (node (ref "D18") (pin "A") (pinfunction "A_A") (pintype "passive"))
      (node (ref "SW16") (pin "P$2") (pinfunction "P$2_P$2") (pintype "passive"))
      (node (ref "SW16") (pin "P$4") (pinfunction "P$4_P$4") (pintype "passive"))
    )
    (net (code "53") (name "Net-(D19-PadA)") (class "Default")
      (node (ref "D19") (pin "A") (pinfunction "A_A") (pintype "passive"))
      (node (ref "SW17") (pin "P$2") (pinfunction "P$2_P$2") (pintype "passive"))
      (node (ref "SW17") (pin "P$4") (pinfunction "P$4_P$4") (pintype "passive"))
    )
    (net (code "54") (name "Net-(D20-PadA)") (class "Default")
      (node (ref "D20") (pin "A") (pinfunction "A_A") (pintype "passive"))
      (node (ref "SW18") (pin "P$2") (pinfunction "P$2_P$2") (pintype "passive"))
      (node (ref "SW18") (pin "P$4") (pinfunction "P$4_P$4") (pintype "passive"))
    )
    (net (code "55") (name "Net-(D21-PadA)") (class "Default")
      (node (ref "D21") (pin "A") (pinfunction "A_A") (pintype "passive"))
      (node (ref "SW19") (pin "P$2") (pinfunction "P$2_P$2") (pintype "passive"))
      (node (ref "SW19") (pin "P$4") (pinfunction "P$4_P$4") (pintype "passive"))
    )
    (net (code "56") (name "Net-(D30-PadA)") (class "Default")
      (node (ref "D30") (pin "A") (pinfunction "A_A") (pintype "passive"))
      (node (ref "SW_4") (pin "P$2") (pinfunction "P$2_P$2") (pintype "passive"))
    )
    (net (code "57") (name "Net-(D31-PadA)") (class "Default")
      (node (ref "D31") (pin "A") (pinfunction "A_A") (pintype "passive"))
      (node (ref "SW_3") (pin "P$2") (pinfunction "P$2_P$2") (pintype "passive"))
    )
    (net (code "58") (name "Net-(IC1-PD0(RXD))") (class "Default")
      (node (ref "IC1") (pin "30") (pinfunction "PD0(RXD)_30") (pintype "bidirectional"))
      (node (ref "TP1") (pin "TP") (pinfunction "TP_TP") (pintype "input"))
    )
    (net (code "59") (name "Net-(IC1-PD1(TXD))") (class "Default")
      (node (ref "IC1") (pin "31") (pinfunction "PD1(TXD)_31") (pintype "bidirectional"))
      (node (ref "TP2") (pin "TP") (pinfunction "TP_TP") (pintype "input"))
    )
    (net (code "60") (name "Net-(X7B-S)") (class "Default")
      (node (ref "D24") (pin "A") (pinfunction "A_A") (pintype "passive"))
      (node (ref "X7") (pin "2") (pinfunction "S_2") (pintype "passive"))
    )
    (net (code "61") (name "Net-(X8B-S)") (class "Default")
      (node (ref "D25") (pin "A") (pinfunction "A_A") (pintype "passive"))
      (node (ref "X8") (pin "2") (pinfunction "S_2") (pintype "passive"))
    )
    (net (code "62") (name "Net-(X10A-S)") (class "Default")
      (node (ref "D29") (pin "A") (pinfunction "A_A") (pintype "passive"))
      (node (ref "X10") (pin "1") (pinfunction "S_1") (pintype "passive"))
    )
    (net (code "63") (name "Net-(X10B-S)") (class "Default")
      (node (ref "D28") (pin "A") (pinfunction "A_A") (pintype "passive"))
      (node (ref "X10") (pin "2") (pinfunction "S_2") (pintype "passive"))
    )
    (net (code "64") (name "Net-(X10C-S)") (class "Default")
      (node (ref "D27") (pin "A") (pinfunction "A_A") (pintype "passive"))
      (node (ref "X10") (pin "3") (pinfunction "S_3") (pintype "passive"))
    )
    (net (code "65") (name "Net-(X10D-S)") (class "Default")
      (node (ref "D26") (pin "A") (pinfunction "A_A") (pintype "passive"))
      (node (ref "X10") (pin "4") (pinfunction "S_4") (pintype "passive"))
    )
    (net (code "66") (name "Net-(X12-P1)") (class "Default")
      (node (ref "F1") (pin "1") (pinfunction "1_1") (pintype "passive"))
      (node (ref "X12") (pin "L1") (pinfunction "P1_L1") (pintype "bidirectional"))
    )
    (net (code "67") (name "VCC") (class "Default")
      (node (ref "C2") (pin "1") (pinfunction "1_1") (pintype "passive"))
      (node (ref "C8") (pin "+") (pinfunction "+_+") (pintype "passive"))
      (node (ref "C9") (pin "1") (pinfunction "1_1") (pintype "passive"))
      (node (ref "D32") (pin "A") (pinfunction "A_A") (pintype "passive"))
      (node (ref "F1") (pin "2") (pinfunction "2_2") (pintype "passive"))
      (node (ref "IC1") (pin "4") (pinfunction "VCC_4") (pintype "bidirectional"))
      (node (ref "IC1") (pin "6") (pinfunction "VCC_6") (pintype "bidirectional"))
      (node (ref "IC2") (pin "6") (pinfunction "G1_6") (pintype "input"))
      (node (ref "JP2") (pin "1") (pinfunction "1_1") (pintype "passive"))
      (node (ref "L1") (pin "1") (pinfunction "1_1") (pintype "passive"))
      (node (ref "R3") (pin "2") (pinfunction "2_2") (pintype "passive"))
    )
    (net (code "68") (name "unconnected-(D8-PadA)") (class "Default")
      (node (ref "D8") (pin "A") (pinfunction "A_A") (pintype "passive"))
    )
    (net (code "69") (name "unconnected-(D13-PadA)") (class "Default")
      (node (ref "D13") (pin "A") (pinfunction "A_A") (pintype "passive"))
    )
    (net (code "70") (name "unconnected-(IC1-ADC6-Pad19)") (class "Default")
      (node (ref "IC1") (pin "19") (pinfunction "ADC6_19") (pintype "bidirectional"))
    )
    (net (code "71") (name "unconnected-(IC1-ADC7-Pad22)") (class "Default")
      (node (ref "IC1") (pin "22") (pinfunction "ADC7_22") (pintype "bidirectional"))
    )
    (net (code "72") (name "unconnected-(IC1-PC0(ADC0)-Pad23)") (class "Default")
      (node (ref "IC1") (pin "23") (pinfunction "PC0(ADC0)_23") (pintype "bidirectional"))
    )
    (net (code "73") (name "unconnected-(SV1-Pad2)") (class "Default")
      (node (ref "SV1") (pin "2") (pinfunction "2_2") (pintype "passive"))
    )
    (net (code "74") (name "unconnected-(X1-S1-PadM1)") (class "Default")
      (node (ref "X1") (pin "M1") (pinfunction "S1_M1") (pintype "passive"))
    )
    (net (code "75") (name "unconnected-(X1-S2-PadM2)") (class "Default")
      (node (ref "X1") (pin "M2") (pinfunction "S2_M2") (pintype "passive"))
    )
  )
)
